# Power_Main_Regulators.net
KiCad netlist of a schematic drawn in Altium Designer
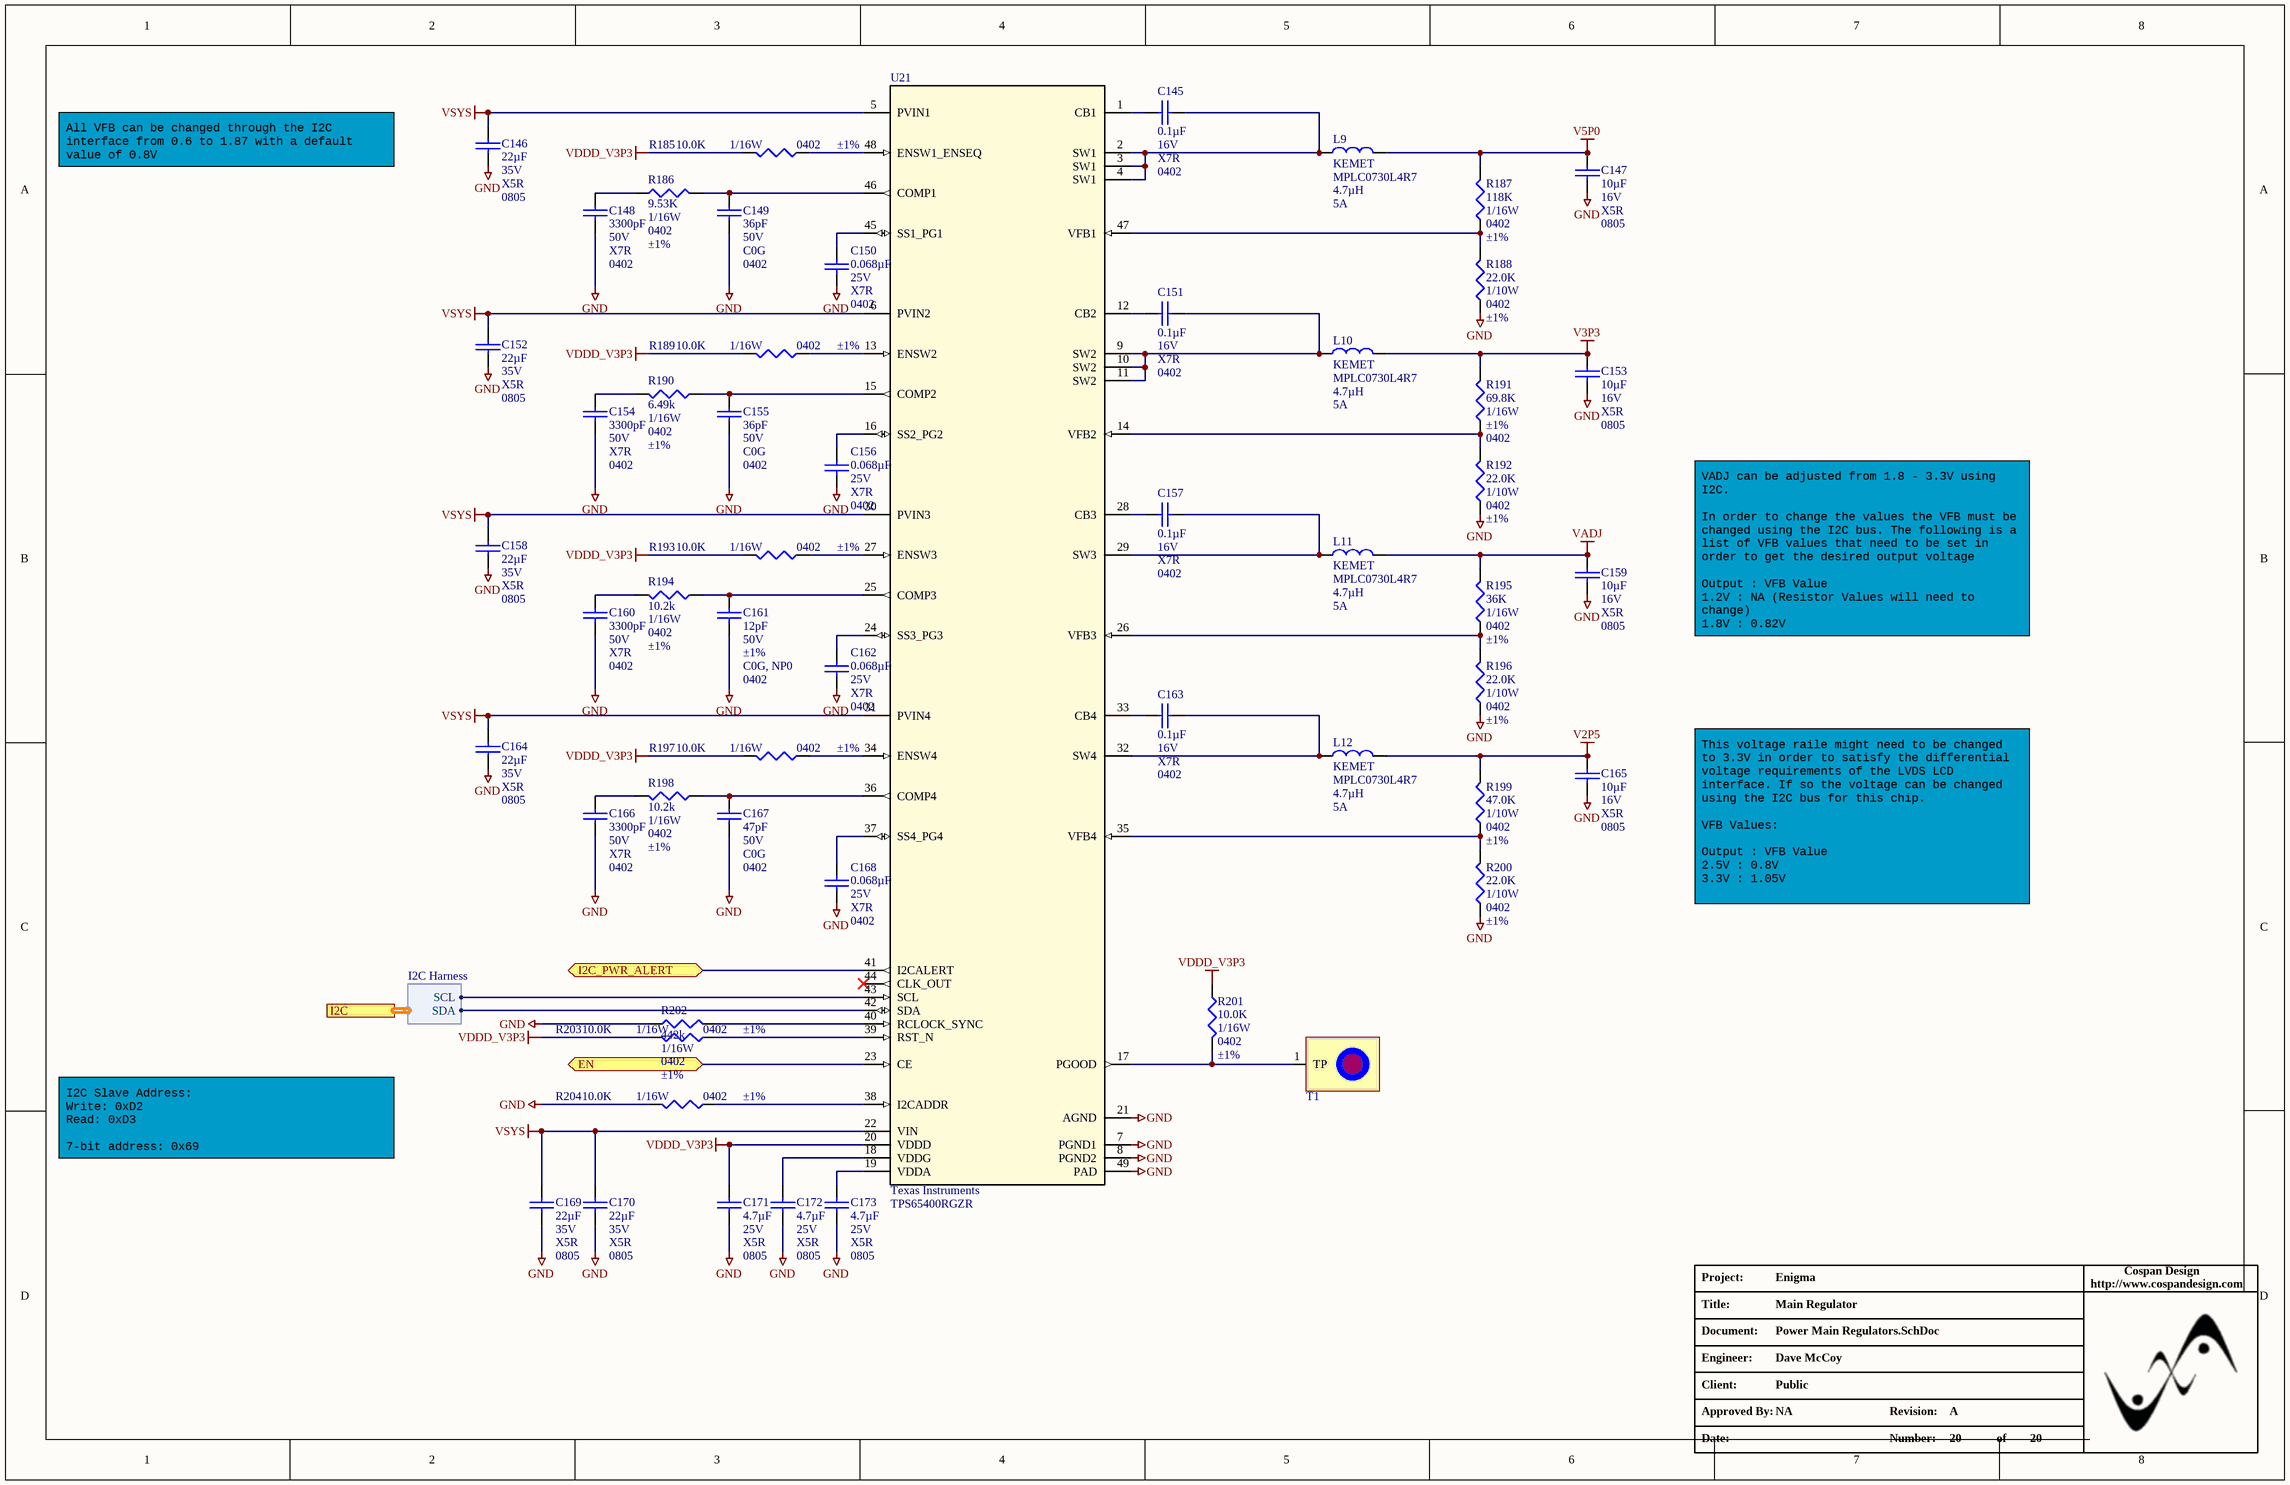
[diagram p0: Power Main Regulators.SchDoc]

(export (version "E")
  (design (tool "Eeschema 10.0.6"))
  (components
    (comp (ref "C145")
      (value "0.1uF")
      (footprint "C_0402")
      (description "CAP CER .10UF 16V X7R 0402")
      (fields
        (field (name "MANUFACTURER") "Murata Electronics North America")
        (field (name "MANUFACTURER PART NUMBER") "GRM155R71C104KA88J")
        (field (name "CAPACITANCE") "0.1µF")
        (field (name "VOLTAGE - RATED") "16V")
        (field (name "TEMPERATURE COEFFICIENT") "X7R")
        (field (name "PACKAGE / CASE") "0402")
      )
      (libsource (lib "Main LibraryX") (part "C_0402_0.1UF_16V"))
    )
    (comp (ref "C146")
      (value "C_0805_22µF_35V")
      (footprint "C_ERA-0805")
      (description "CAP CER 22UF 35V X5R 0805")
      (fields
        (field (name "MANUFACTURER") "TDK Corporation")
        (field (name "MANUFACTURER PART NUMBER") "C2012X5R1V226M125AC")
        (field (name "CAPACITANCE") "22µF")
        (field (name "VOLTAGE - RATED") "35V")
        (field (name "TEMPERATURE COEFFICIENT") "X5R")
        (field (name "PACKAGE / CASE") "0805")
      )
      (libsource (lib "Cospan Design") (part "C_0805_22µF_35V"))
    )
    (comp (ref "C147")
      (value "10µF")
      (footprint "C_ERA-0805")
      (description "CAP CER 10uF 16V X5R 20% 0805")
      (fields
        (field (name "MANUFACTURER") "Taiyo Yuden")
        (field (name "MANUFACTURER PART NUMBER") "EMK212BJ106KG-T")
        (field (name "CAPACITANCE") "10µF")
        (field (name "VOLTAGE - RATED") "16V")
        (field (name "TEMPERATURE COEFFICIENT") "X5R")
        (field (name "PACKAGE / CASE") "0805")
      )
      (libsource (lib "Main LibraryX") (part "C_0805_10UF_16V"))
    )
    (comp (ref "C148")
      (value "C_0402_3.3nF_50V")
      (footprint "C_ERA-0402")
      (fields
        (field (name "MANUFACTURER") "Murata Electronics North America")
        (field (name "MANUFACTURER PART NUMBER") "GRM155R71H332KA01D")
        (field (name "TOLERANCE") "±10%")
        (field (name "CAPACITANCE") "3300pF")
        (field (name "VOLTAGE - RATED") "50V")
        (field (name "TEMPERATURE COEFFICIENT") "X7R")
        (field (name "PACKAGE / CASE") "0402")
      )
      (libsource (lib "Main LibraryX") (part "C_0402_3.3nF_50V"))
    )
    (comp (ref "C149")
      (value "C_0402_36pF")
      (footprint "C_0402")
      (description "CAP CER 36PF 50V NP0 0402")
      (fields
        (field (name "MANUFACTURER") "Samsung Electro-Mechanics America, Inc.")
        (field (name "MANUFACTURER PART NUMBER") "CL05C360JB5NNNC")
        (field (name "CAPACITANCE") "36pF")
        (field (name "VOLTAGE - RATED") "50V")
        (field (name "TEMPERATURE COEFFICIENT") "C0G")
        (field (name "PACKAGE / CASE") "0402")
      )
      (libsource (lib "Cospan Design") (part "C_0402_36pF"))
    )
    (comp (ref "C150")
      (value "C_0402_68nF")
      (footprint "C_0402")
      (description "CAP CER 0.068UF 25V X7R 0402")
      (fields
        (field (name "MANUFACTURER") "Murata Electronics North America")
        (field (name "MANUFACTURER PART NUMBER") "GRM155R71E683KE14D")
        (field (name "CAPACITANCE") "0.068µF")
        (field (name "VOLTAGE - RATED") "25V")
        (field (name "TEMPERATURE COEFFICIENT") "X7R")
        (field (name "PACKAGE / CASE") "0402")
      )
      (libsource (lib "Cospan Design") (part "C_0402_68nF"))
    )
    (comp (ref "C151")
      (value "0.1uF")
      (footprint "C_0402")
      (description "CAP CER .10UF 16V X7R 0402")
      (fields
        (field (name "MANUFACTURER") "Murata Electronics North America")
        (field (name "MANUFACTURER PART NUMBER") "GRM155R71C104KA88J")
        (field (name "CAPACITANCE") "0.1µF")
        (field (name "VOLTAGE - RATED") "16V")
        (field (name "TEMPERATURE COEFFICIENT") "X7R")
        (field (name "PACKAGE / CASE") "0402")
      )
      (libsource (lib "Main LibraryX") (part "C_0402_0.1UF_16V"))
    )
    (comp (ref "C152")
      (value "C_0805_22µF_35V")
      (footprint "C_ERA-0805")
      (description "CAP CER 22UF 35V X5R 0805")
      (fields
        (field (name "MANUFACTURER") "TDK Corporation")
        (field (name "MANUFACTURER PART NUMBER") "C2012X5R1V226M125AC")
        (field (name "CAPACITANCE") "22µF")
        (field (name "VOLTAGE - RATED") "35V")
        (field (name "TEMPERATURE COEFFICIENT") "X5R")
        (field (name "PACKAGE / CASE") "0805")
      )
      (libsource (lib "Cospan Design") (part "C_0805_22µF_35V"))
    )
    (comp (ref "C153")
      (value "10µF")
      (footprint "C_ERA-0805")
      (description "CAP CER 10uF 16V X5R 20% 0805")
      (fields
        (field (name "MANUFACTURER") "Taiyo Yuden")
        (field (name "MANUFACTURER PART NUMBER") "EMK212BJ106KG-T")
        (field (name "CAPACITANCE") "10µF")
        (field (name "VOLTAGE - RATED") "16V")
        (field (name "TEMPERATURE COEFFICIENT") "X5R")
        (field (name "PACKAGE / CASE") "0805")
      )
      (libsource (lib "Main LibraryX") (part "C_0805_10UF_16V"))
    )
    (comp (ref "C154")
      (value "C_0402_3.3nF_50V")
      (footprint "C_ERA-0402")
      (fields
        (field (name "MANUFACTURER") "Murata Electronics North America")
        (field (name "MANUFACTURER PART NUMBER") "GRM155R71H332KA01D")
        (field (name "TOLERANCE") "±10%")
        (field (name "CAPACITANCE") "3300pF")
        (field (name "VOLTAGE - RATED") "50V")
        (field (name "TEMPERATURE COEFFICIENT") "X7R")
        (field (name "PACKAGE / CASE") "0402")
      )
      (libsource (lib "Main LibraryX") (part "C_0402_3.3nF_50V"))
    )
    (comp (ref "C155")
      (value "C_0402_36pF")
      (footprint "C_0402")
      (description "CAP CER 36PF 50V NP0 0402")
      (fields
        (field (name "MANUFACTURER") "Samsung Electro-Mechanics America, Inc.")
        (field (name "MANUFACTURER PART NUMBER") "CL05C360JB5NNNC")
        (field (name "CAPACITANCE") "36pF")
        (field (name "VOLTAGE - RATED") "50V")
        (field (name "TEMPERATURE COEFFICIENT") "C0G")
        (field (name "PACKAGE / CASE") "0402")
      )
      (libsource (lib "Cospan Design") (part "C_0402_36pF"))
    )
    (comp (ref "C156")
      (value "C_0402_68nF")
      (footprint "C_0402")
      (description "CAP CER 0.068UF 25V X7R 0402")
      (fields
        (field (name "MANUFACTURER") "Murata Electronics North America")
        (field (name "MANUFACTURER PART NUMBER") "GRM155R71E683KE14D")
        (field (name "CAPACITANCE") "0.068µF")
        (field (name "VOLTAGE - RATED") "25V")
        (field (name "TEMPERATURE COEFFICIENT") "X7R")
        (field (name "PACKAGE / CASE") "0402")
      )
      (libsource (lib "Cospan Design") (part "C_0402_68nF"))
    )
    (comp (ref "C157")
      (value "0.1uF")
      (footprint "C_0402")
      (description "CAP CER .10UF 16V X7R 0402")
      (fields
        (field (name "MANUFACTURER") "Murata Electronics North America")
        (field (name "MANUFACTURER PART NUMBER") "GRM155R71C104KA88J")
        (field (name "CAPACITANCE") "0.1µF")
        (field (name "VOLTAGE - RATED") "16V")
        (field (name "TEMPERATURE COEFFICIENT") "X7R")
        (field (name "PACKAGE / CASE") "0402")
      )
      (libsource (lib "Main LibraryX") (part "C_0402_0.1UF_16V"))
    )
    (comp (ref "C158")
      (value "C_0805_22µF_35V")
      (footprint "C_ERA-0805")
      (description "CAP CER 22UF 35V X5R 0805")
      (fields
        (field (name "MANUFACTURER") "TDK Corporation")
        (field (name "MANUFACTURER PART NUMBER") "C2012X5R1V226M125AC")
        (field (name "CAPACITANCE") "22µF")
        (field (name "VOLTAGE - RATED") "35V")
        (field (name "TEMPERATURE COEFFICIENT") "X5R")
        (field (name "PACKAGE / CASE") "0805")
      )
      (libsource (lib "Cospan Design") (part "C_0805_22µF_35V"))
    )
    (comp (ref "C159")
      (value "10µF")
      (footprint "C_ERA-0805")
      (description "CAP CER 10uF 16V X5R 20% 0805")
      (fields
        (field (name "MANUFACTURER") "Taiyo Yuden")
        (field (name "MANUFACTURER PART NUMBER") "EMK212BJ106KG-T")
        (field (name "CAPACITANCE") "10µF")
        (field (name "VOLTAGE - RATED") "16V")
        (field (name "TEMPERATURE COEFFICIENT") "X5R")
        (field (name "PACKAGE / CASE") "0805")
      )
      (libsource (lib "Main LibraryX") (part "C_0805_10UF_16V"))
    )
    (comp (ref "C160")
      (value "C_0402_3.3nF_50V")
      (footprint "C_ERA-0402")
      (fields
        (field (name "MANUFACTURER") "Murata Electronics North America")
        (field (name "MANUFACTURER PART NUMBER") "GRM155R71H332KA01D")
        (field (name "TOLERANCE") "±10%")
        (field (name "CAPACITANCE") "3300pF")
        (field (name "VOLTAGE - RATED") "50V")
        (field (name "TEMPERATURE COEFFICIENT") "X7R")
        (field (name "PACKAGE / CASE") "0402")
      )
      (libsource (lib "Main LibraryX") (part "C_0402_3.3nF_50V"))
    )
    (comp (ref "C161")
      (value "12pF")
      (footprint "C_ERA-0402")
      (description "CAP CER 12PF 50V 5% C0G 0402")
      (fields
        (field (name "MANUFACTURER") "Murata Electronics North America")
        (field (name "MANUFACTURER PART NUMBER") "GRM1555C1H120FA01D")
        (field (name "CAPACITANCE") "12pF")
        (field (name "VOLTAGE - RATED") "50V")
        (field (name "TOLERANCE") "±1%")
        (field (name "TEMPERATURE COEFFICIENT") "C0G, NP0")
        (field (name "PACKAGE / CASE") "0402")
      )
      (libsource (lib "Main LibraryX") (part "C_0402_12PF_50V"))
    )
    (comp (ref "C162")
      (value "C_0402_68nF")
      (footprint "C_0402")
      (description "CAP CER 0.068UF 25V X7R 0402")
      (fields
        (field (name "MANUFACTURER") "Murata Electronics North America")
        (field (name "MANUFACTURER PART NUMBER") "GRM155R71E683KE14D")
        (field (name "CAPACITANCE") "0.068µF")
        (field (name "VOLTAGE - RATED") "25V")
        (field (name "TEMPERATURE COEFFICIENT") "X7R")
        (field (name "PACKAGE / CASE") "0402")
      )
      (libsource (lib "Cospan Design") (part "C_0402_68nF"))
    )
    (comp (ref "C163")
      (value "0.1uF")
      (footprint "C_0402")
      (description "CAP CER .10UF 16V X7R 0402")
      (fields
        (field (name "MANUFACTURER") "Murata Electronics North America")
        (field (name "MANUFACTURER PART NUMBER") "GRM155R71C104KA88J")
        (field (name "CAPACITANCE") "0.1µF")
        (field (name "VOLTAGE - RATED") "16V")
        (field (name "TEMPERATURE COEFFICIENT") "X7R")
        (field (name "PACKAGE / CASE") "0402")
      )
      (libsource (lib "Main LibraryX") (part "C_0402_0.1UF_16V"))
    )
    (comp (ref "C164")
      (value "C_0805_22µF_35V")
      (footprint "C_ERA-0805")
      (description "CAP CER 22UF 35V X5R 0805")
      (fields
        (field (name "MANUFACTURER") "TDK Corporation")
        (field (name "MANUFACTURER PART NUMBER") "C2012X5R1V226M125AC")
        (field (name "CAPACITANCE") "22µF")
        (field (name "VOLTAGE - RATED") "35V")
        (field (name "TEMPERATURE COEFFICIENT") "X5R")
        (field (name "PACKAGE / CASE") "0805")
      )
      (libsource (lib "Cospan Design") (part "C_0805_22µF_35V"))
    )
    (comp (ref "C165")
      (value "10µF")
      (footprint "C_ERA-0805")
      (description "CAP CER 10uF 16V X5R 20% 0805")
      (fields
        (field (name "MANUFACTURER") "Taiyo Yuden")
        (field (name "MANUFACTURER PART NUMBER") "EMK212BJ106KG-T")
        (field (name "CAPACITANCE") "10µF")
        (field (name "VOLTAGE - RATED") "16V")
        (field (name "TEMPERATURE COEFFICIENT") "X5R")
        (field (name "PACKAGE / CASE") "0805")
      )
      (libsource (lib "Main LibraryX") (part "C_0805_10UF_16V"))
    )
    (comp (ref "C166")
      (value "C_0402_3.3nF_50V")
      (footprint "C_ERA-0402")
      (fields
        (field (name "MANUFACTURER") "Murata Electronics North America")
        (field (name "MANUFACTURER PART NUMBER") "GRM155R71H332KA01D")
        (field (name "TOLERANCE") "±10%")
        (field (name "CAPACITANCE") "3300pF")
        (field (name "VOLTAGE - RATED") "50V")
        (field (name "TEMPERATURE COEFFICIENT") "X7R")
        (field (name "PACKAGE / CASE") "0402")
      )
      (libsource (lib "Main LibraryX") (part "C_0402_3.3nF_50V"))
    )
    (comp (ref "C167")
      (value "47pF")
      (footprint "C_0402")
      (description "CAP CER 47PF 50V 5% C0G 0402")
      (fields
        (field (name "MANUFACTURER") "Murata Electronics North America")
        (field (name "MANUFACTURER PART NUMBER") "GRM1555C1H470JA01D")
        (field (name "CAPACITANCE") "47pF")
        (field (name "VOLTAGE - RATED") "50V")
        (field (name "TEMPERATURE COEFFICIENT") "C0G")
        (field (name "PACKAGE / CASE") "0402")
      )
      (libsource (lib "Main Library") (part "C_0402_47p_50V"))
    )
    (comp (ref "C168")
      (value "C_0402_68nF")
      (footprint "C_0402")
      (description "CAP CER 0.068UF 25V X7R 0402")
      (fields
        (field (name "MANUFACTURER") "Murata Electronics North America")
        (field (name "MANUFACTURER PART NUMBER") "GRM155R71E683KE14D")
        (field (name "CAPACITANCE") "0.068µF")
        (field (name "VOLTAGE - RATED") "25V")
        (field (name "TEMPERATURE COEFFICIENT") "X7R")
        (field (name "PACKAGE / CASE") "0402")
      )
      (libsource (lib "Cospan Design") (part "C_0402_68nF"))
    )
    (comp (ref "C169")
      (value "C_0805_22µF_35V")
      (footprint "C_ERA-0805")
      (description "CAP CER 22UF 35V X5R 0805")
      (fields
        (field (name "MANUFACTURER") "TDK Corporation")
        (field (name "MANUFACTURER PART NUMBER") "C2012X5R1V226M125AC")
        (field (name "CAPACITANCE") "22µF")
        (field (name "VOLTAGE - RATED") "35V")
        (field (name "TEMPERATURE COEFFICIENT") "X5R")
        (field (name "PACKAGE / CASE") "0805")
      )
      (libsource (lib "Cospan Design") (part "C_0805_22µF_35V"))
    )
    (comp (ref "C170")
      (value "C_0805_22µF_35V")
      (footprint "C_ERA-0805")
      (description "CAP CER 22UF 35V X5R 0805")
      (fields
        (field (name "MANUFACTURER") "TDK Corporation")
        (field (name "MANUFACTURER PART NUMBER") "C2012X5R1V226M125AC")
        (field (name "CAPACITANCE") "22µF")
        (field (name "VOLTAGE - RATED") "35V")
        (field (name "TEMPERATURE COEFFICIENT") "X5R")
        (field (name "PACKAGE / CASE") "0805")
      )
      (libsource (lib "Cospan Design") (part "C_0805_22µF_35V"))
    )
    (comp (ref "C171")
      (value "4.7µF")
      (footprint "C_ERA-0805")
      (description "CAP CER 4.7UF 25V 10% X5R 0805")
      (fields
        (field (name "MANUFACTURER") "Taiyo Yuden")
        (field (name "MANUFACTURER PART NUMBER") "TMK212BJ475KG-T")
        (field (name "CAPACITANCE") "4.7µF")
        (field (name "VOLTAGE - RATED") "25V")
        (field (name "TEMPERATURE COEFFICIENT") "X5R")
        (field (name "PACKAGE / CASE") "0805")
      )
      (libsource (lib "Main Library") (part "C_0805_4.7µF_25V"))
    )
    (comp (ref "C172")
      (value "4.7µF")
      (footprint "C_ERA-0805")
      (description "CAP CER 4.7UF 25V 10% X5R 0805")
      (fields
        (field (name "MANUFACTURER") "Taiyo Yuden")
        (field (name "MANUFACTURER PART NUMBER") "TMK212BJ475KG-T")
        (field (name "CAPACITANCE") "4.7µF")
        (field (name "VOLTAGE - RATED") "25V")
        (field (name "TEMPERATURE COEFFICIENT") "X5R")
        (field (name "PACKAGE / CASE") "0805")
      )
      (libsource (lib "Main Library") (part "C_0805_4.7µF_25V"))
    )
    (comp (ref "C173")
      (value "4.7µF")
      (footprint "C_ERA-0805")
      (description "CAP CER 4.7UF 25V 10% X5R 0805")
      (fields
        (field (name "MANUFACTURER") "Taiyo Yuden")
        (field (name "MANUFACTURER PART NUMBER") "TMK212BJ475KG-T")
        (field (name "CAPACITANCE") "4.7µF")
        (field (name "VOLTAGE - RATED") "25V")
        (field (name "TEMPERATURE COEFFICIENT") "X5R")
        (field (name "PACKAGE / CASE") "0805")
      )
      (libsource (lib "Main Library") (part "C_0805_4.7µF_25V"))
    )
    (comp (ref "L9")
      (value "L_MPLC0730L4R7")
      (footprint "KEM_L9004_MPLC")
      (description "FIXED IND 4.7UH 5A 41 MOHM SMD")
      (fields
        (field (name "TOLERANCE") "±20%")
        (field (name "MANUFACTURER") "KEMET")
        (field (name "MANUFACTURER PART NUMBER") "MPLC0730L4R7")
        (field (name "INDUCTANCE") "4.7µH")
        (field (name "MAX DC CURRENT") "5A")
      )
      (libsource (lib "Cospan Design") (part "L_MPLC0730L4R7"))
    )
    (comp (ref "L10")
      (value "L_MPLC0730L4R7")
      (footprint "KEM_L9004_MPLC")
      (description "FIXED IND 4.7UH 5A 41 MOHM SMD")
      (fields
        (field (name "TOLERANCE") "±20%")
        (field (name "MANUFACTURER") "KEMET")
        (field (name "MANUFACTURER PART NUMBER") "MPLC0730L4R7")
        (field (name "INDUCTANCE") "4.7µH")
        (field (name "MAX DC CURRENT") "5A")
      )
      (libsource (lib "Cospan Design") (part "L_MPLC0730L4R7"))
    )
    (comp (ref "L11")
      (value "L_MPLC0730L4R7")
      (footprint "KEM_L9004_MPLC")
      (description "FIXED IND 4.7UH 5A 41 MOHM SMD")
      (fields
        (field (name "TOLERANCE") "±20%")
        (field (name "MANUFACTURER") "KEMET")
        (field (name "MANUFACTURER PART NUMBER") "MPLC0730L4R7")
        (field (name "INDUCTANCE") "4.7µH")
        (field (name "MAX DC CURRENT") "5A")
      )
      (libsource (lib "Cospan Design") (part "L_MPLC0730L4R7"))
    )
    (comp (ref "L12")
      (value "L_MPLC0730L4R7")
      (footprint "KEM_L9004_MPLC")
      (description "FIXED IND 4.7UH 5A 41 MOHM SMD")
      (fields
        (field (name "TOLERANCE") "±20%")
        (field (name "MANUFACTURER") "KEMET")
        (field (name "MANUFACTURER PART NUMBER") "MPLC0730L4R7")
        (field (name "INDUCTANCE") "4.7µH")
        (field (name "MAX DC CURRENT") "5A")
      )
      (libsource (lib "Cospan Design") (part "L_MPLC0730L4R7"))
    )
    (comp (ref "R185")
      (value "R_0402_10.0K")
      (footprint "R_0402")
      (description "RES 10.0K OHM 1/16W 1% 0402 SMD")
      (fields
        (field (name "MANUFACTURER") "Stackpole Electronics Inc")
        (field (name "MANUFACTURER PART NUMBER") "RMCF0402FT10K0")
        (field (name "RESISTANCE IN OHMS") "10.0K")
        (field (name "POWER (WATTS)") "1/16W")
        (field (name "CASE") "0402")
        (field (name "TOLERANCE") "±1%")
      )
      (libsource (lib "Cospan Design") (part "R_0402_10.0K"))
    )
    (comp (ref "R186")
      (value "R_0402_9.53K")
      (footprint "R_0402")
      (description "RES SMD 9.53K OHM 1% 1/16W 0402")
      (fields
        (field (name "MANUFACTURER") "Yageo")
        (field (name "MANUFACTURER PART NUMBER") "RC0402FR-079K53L")
        (field (name "RESISTANCE IN OHMS") "9.53K")
        (field (name "POWER (WATTS)") "1/16W")
        (field (name "CASE") "0402")
        (field (name "TOLERANCE") "±1%")
      )
      (libsource (lib "Cospan Design") (part "R_0402_9.53K"))
    )
    (comp (ref "R187")
      (value "R_0402_118K")
      (footprint "R_0402")
      (description "RES SMD 118K OHM 1% 1/16W 0402")
      (fields
        (field (name "MANUFACTURER") "Stackpole Electronics Inc")
        (field (name "MANUFACTURER PART NUMBER") "RMCF0402FT118K")
        (field (name "RESISTANCE IN OHMS") "118K")
        (field (name "POWER (WATTS)") "1/16W")
        (field (name "CASE") "0402")
        (field (name "TOLERANCE") "±1%")
      )
      (libsource (lib "Cospan Design") (part "R_0402_118K"))
    )
    (comp (ref "R188")
      (value "R_0402_22.0K")
      (footprint "R_0402")
      (description "RES 22.0K OHM 1/10W 1% 0402 SMD")
      (fields
        (field (name "MANUFACTURER") "Vishay Dale")
        (field (name "MANUFACTURER PART NUMBER") "CRCW040222K0FKED")
        (field (name "RESISTANCE IN OHMS") "22.0K")
        (field (name "POWER (WATTS)") "1/10W")
        (field (name "CASE") "0402")
        (field (name "TOLERANCE") "±1%")
      )
      (libsource (lib "Main Library") (part "R_0402_22.0K"))
    )
    (comp (ref "R189")
      (value "R_0402_10.0K")
      (footprint "R_0402")
      (description "RES 10.0K OHM 1/16W 1% 0402 SMD")
      (fields
        (field (name "MANUFACTURER") "Stackpole Electronics Inc")
        (field (name "MANUFACTURER PART NUMBER") "RMCF0402FT10K0")
        (field (name "RESISTANCE IN OHMS") "10.0K")
        (field (name "POWER (WATTS)") "1/16W")
        (field (name "CASE") "0402")
        (field (name "TOLERANCE") "±1%")
      )
      (libsource (lib "Cospan Design") (part "R_0402_10.0K"))
    )
    (comp (ref "R190")
      (value "R_0402_6.49k")
      (footprint "R_0402")
      (description "RES SMD 6.49K OHM 1% 1/16W 0402")
      (fields
        (field (name "MANUFACTURER") "Samsung Electro-Mechanics America, Inc.")
        (field (name "MANUFACTURER PART NUMBER") "RC1005F6491CS")
        (field (name "RESISTANCE IN OHMS") "6.49k")
        (field (name "POWER (WATTS)") "1/16W")
        (field (name "CASE") "0402")
        (field (name "TOLERANCE") "±1%")
      )
      (libsource (lib "Cospan Design") (part "R_0402_6.49k"))
    )
    (comp (ref "R191")
      (value "R_0402_69.8K")
      (footprint "R_0402")
      (description "RES 69.8K OHM 1/16W 1% 0402 SMD")
      (fields
        (field (name "MANUFACTURER") "Yageo")
        (field (name "MANUFACTURER PART NUMBER") "RC0402FR-0769K8L")
        (field (name "RESISTANCE IN OHMS") "69.8K")
        (field (name "POWER (WATTS)") "1/16W")
        (field (name "TOLERANCE") "±1%")
        (field (name "CASE") "0402")
      )
      (libsource (lib "Main LibraryX") (part "R_0402_69.8K"))
    )
    (comp (ref "R192")
      (value "R_0402_22.0K")
      (footprint "R_0402")
      (description "RES 22.0K OHM 1/10W 1% 0402 SMD")
      (fields
        (field (name "MANUFACTURER") "Vishay Dale")
        (field (name "MANUFACTURER PART NUMBER") "CRCW040222K0FKED")
        (field (name "RESISTANCE IN OHMS") "22.0K")
        (field (name "POWER (WATTS)") "1/10W")
        (field (name "CASE") "0402")
        (field (name "TOLERANCE") "±1%")
      )
      (libsource (lib "Main Library") (part "R_0402_22.0K"))
    )
    (comp (ref "R193")
      (value "R_0402_10.0K")
      (footprint "R_0402")
      (description "RES 10.0K OHM 1/16W 1% 0402 SMD")
      (fields
        (field (name "MANUFACTURER") "Stackpole Electronics Inc")
        (field (name "MANUFACTURER PART NUMBER") "RMCF0402FT10K0")
        (field (name "RESISTANCE IN OHMS") "10.0K")
        (field (name "POWER (WATTS)") "1/16W")
        (field (name "CASE") "0402")
        (field (name "TOLERANCE") "±1%")
      )
      (libsource (lib "Cospan Design") (part "R_0402_10.0K"))
    )
    (comp (ref "R194")
      (value "R_0402_10.2k")
      (footprint "R_0402")
      (description "RES SMD 10.2K OHM 1% 1/16W 0402")
      (fields
        (field (name "MANUFACTURER") "Stackpole Electronics Inc.")
        (field (name "MANUFACTURER PART NUMBER") "RMCF0402FT10K2")
        (field (name "RESISTANCE IN OHMS") "10.2k")
        (field (name "POWER (WATTS)") "1/16W")
        (field (name "CASE") "0402")
        (field (name "TOLERANCE") "±1%")
      )
      (libsource (lib "Cospan Design") (part "R_0402_10.2k"))
    )
    (comp (ref "R195")
      (value "R_0402_36.0K")
      (footprint "R_0402")
      (description "RES 36.0K OHM 1/10W 1% 0402 SMD")
      (fields
        (field (name "MANUFACTURER") "Panasonic - ECG")
        (field (name "MANUFACTURER PART NUMBER") "ERJ-2RKF3602X")
        (field (name "RESISTANCE IN OHMS") "36K")
        (field (name "POWER (WATTS)") "1/16W")
        (field (name "CASE") "0402")
        (field (name "TOLERANCE") "±1%")
      )
      (libsource (lib "Main Library") (part "R_0402_36.0K"))
    )
    (comp (ref "R196")
      (value "R_0402_22.0K")
      (footprint "R_0402")
      (description "RES 22.0K OHM 1/10W 1% 0402 SMD")
      (fields
        (field (name "MANUFACTURER") "Vishay Dale")
        (field (name "MANUFACTURER PART NUMBER") "CRCW040222K0FKED")
        (field (name "RESISTANCE IN OHMS") "22.0K")
        (field (name "POWER (WATTS)") "1/10W")
        (field (name "CASE") "0402")
        (field (name "TOLERANCE") "±1%")
      )
      (libsource (lib "Main Library") (part "R_0402_22.0K"))
    )
    (comp (ref "R197")
      (value "R_0402_10.0K")
      (footprint "R_0402")
      (description "RES 10.0K OHM 1/16W 1% 0402 SMD")
      (fields
        (field (name "MANUFACTURER") "Stackpole Electronics Inc")
        (field (name "MANUFACTURER PART NUMBER") "RMCF0402FT10K0")
        (field (name "RESISTANCE IN OHMS") "10.0K")
        (field (name "POWER (WATTS)") "1/16W")
        (field (name "CASE") "0402")
        (field (name "TOLERANCE") "±1%")
      )
      (libsource (lib "Cospan Design") (part "R_0402_10.0K"))
    )
    (comp (ref "R198")
      (value "R_0402_10.2k")
      (footprint "R_0402")
      (description "RES SMD 10.2K OHM 1% 1/16W 0402")
      (fields
        (field (name "MANUFACTURER") "Stackpole Electronics Inc.")
        (field (name "MANUFACTURER PART NUMBER") "RMCF0402FT10K2")
        (field (name "RESISTANCE IN OHMS") "10.2k")
        (field (name "POWER (WATTS)") "1/16W")
        (field (name "CASE") "0402")
        (field (name "TOLERANCE") "±1%")
      )
      (libsource (lib "Cospan Design") (part "R_0402_10.2k"))
    )
    (comp (ref "R199")
      (value "R_0402_47.0K")
      (footprint "R_0402")
      (description "RES 47.0K OHM 1/10W 1% 0402 SMD")
      (fields
        (field (name "MANUFACTURER") "Panasonic - ECG")
        (field (name "MANUFACTURER PART NUMBER") "ERJ-2RKF4702X")
        (field (name "RESISTANCE IN OHMS") "47.0K")
        (field (name "POWER (WATTS)") "1/10W")
        (field (name "CASE") "0402")
        (field (name "TOLERANCE") "±1%")
      )
      (libsource (lib "Main Library") (part "R_0402_47.0K"))
    )
    (comp (ref "R200")
      (value "R_0402_22.0K")
      (footprint "R_0402")
      (description "RES 22.0K OHM 1/10W 1% 0402 SMD")
      (fields
        (field (name "MANUFACTURER") "Vishay Dale")
        (field (name "MANUFACTURER PART NUMBER") "CRCW040222K0FKED")
        (field (name "RESISTANCE IN OHMS") "22.0K")
        (field (name "POWER (WATTS)") "1/10W")
        (field (name "CASE") "0402")
        (field (name "TOLERANCE") "±1%")
      )
      (libsource (lib "Main Library") (part "R_0402_22.0K"))
    )
    (comp (ref "R201")
      (value "R_0402_10.0K")
      (footprint "R_0402")
      (description "RES 10.0K OHM 1/16W 1% 0402 SMD")
      (fields
        (field (name "MANUFACTURER") "Stackpole Electronics Inc")
        (field (name "MANUFACTURER PART NUMBER") "RMCF0402FT10K0")
        (field (name "RESISTANCE IN OHMS") "10.0K")
        (field (name "POWER (WATTS)") "1/16W")
        (field (name "CASE") "0402")
        (field (name "TOLERANCE") "±1%")
      )
      (libsource (lib "Cospan Design") (part "R_0402_10.0K"))
    )
    (comp (ref "R202")
      (value "R_0402_442k")
      (footprint "R_0402")
      (description "RES SMD 442K OHM 1% 1/16W 0402")
      (fields
        (field (name "MANUFACTURER") "Yageo")
        (field (name "MANUFACTURER PART NUMBER") "RC0402FR-07442KL")
        (field (name "RESISTANCE IN OHMS") "442k")
        (field (name "POWER (WATTS)") "1/16W")
        (field (name "CASE") "0402")
        (field (name "TOLERANCE") "±1%")
      )
      (libsource (lib "Cospan Design") (part "R_0402_442k"))
    )
    (comp (ref "R203")
      (value "R_0402_10.0K")
      (footprint "R_0402")
      (description "RES 10.0K OHM 1/16W 1% 0402 SMD")
      (fields
        (field (name "MANUFACTURER") "Stackpole Electronics Inc")
        (field (name "MANUFACTURER PART NUMBER") "RMCF0402FT10K0")
        (field (name "RESISTANCE IN OHMS") "10.0K")
        (field (name "POWER (WATTS)") "1/16W")
        (field (name "CASE") "0402")
        (field (name "TOLERANCE") "±1%")
      )
      (libsource (lib "Cospan Design") (part "R_0402_10.0K"))
    )
    (comp (ref "R204")
      (value "R_0402_10.0K")
      (footprint "R_0402")
      (description "RES 10.0K OHM 1/16W 1% 0402 SMD")
      (fields
        (field (name "MANUFACTURER") "Stackpole Electronics Inc")
        (field (name "MANUFACTURER PART NUMBER") "RMCF0402FT10K0")
        (field (name "RESISTANCE IN OHMS") "10.0K")
        (field (name "POWER (WATTS)") "1/16W")
        (field (name "CASE") "0402")
        (field (name "TOLERANCE") "±1%")
      )
      (libsource (lib "Cospan Design") (part "R_0402_10.0K"))
    )
    (comp (ref "T1")
      (value "TEST_POINT_SMALL")
      (footprint "TestPointSmall")
      (description "OSCILLOSCOPE TEST POINT")
      (libsource (lib "Main Library") (part "TEST_POINT_SMALL"))
    )
    (comp (ref "U21")
      (value "U_TPS65400RGZR")
      (footprint "RGZ0048B")
      (description "IC REG BUCK ADJ 4A/2A QD 48VQFN")
      (fields
        (field (name "MANUFACTURER") "Texas Instruments")
        (field (name "MANUFACTURER PART NUMBER") "TPS65400RGZR")
      )
      (libsource (lib "Cospan Design") (part "U_TPS65400RGZR"))
    )
  )
  (nets
    (net (code "3") (name "/EN") (class "Default")
      (node (ref "U21") (pin "23") (pinfunction "CE_23") (pintype "input"))
    )
    (net (code "4") (name "/I2C_PWR_ALERT") (class "Default")
      (node (ref "U21") (pin "41") (pinfunction "I2CALERT_41") (pintype "output"))
    )
    (net (code "5") (name "/SCL") (class "Default")
      (node (ref "U21") (pin "43") (pinfunction "SCL_43") (pintype "input"))
    )
    (net (code "6") (name "/SDA") (class "Default")
      (node (ref "U21") (pin "42") (pinfunction "SDA_42") (pintype "bidirectional"))
    )
    (net (code "8") (name "GND") (class "Default")
      (node (ref "C146") (pin "1") (pinfunction "1_1") (pintype "passive"))
      (node (ref "C147") (pin "1") (pinfunction "1_1") (pintype "passive"))
      (node (ref "C148") (pin "1") (pinfunction "1_1") (pintype "passive"))
      (node (ref "C149") (pin "1") (pinfunction "1_1") (pintype "passive"))
      (node (ref "C150") (pin "1") (pinfunction "1_1") (pintype "passive"))
      (node (ref "C152") (pin "1") (pinfunction "1_1") (pintype "passive"))
      (node (ref "C153") (pin "1") (pinfunction "1_1") (pintype "passive"))
      (node (ref "C154") (pin "1") (pinfunction "1_1") (pintype "passive"))
      (node (ref "C155") (pin "1") (pinfunction "1_1") (pintype "passive"))
      (node (ref "C156") (pin "1") (pinfunction "1_1") (pintype "passive"))
      (node (ref "C158") (pin "1") (pinfunction "1_1") (pintype "passive"))
      (node (ref "C159") (pin "1") (pinfunction "1_1") (pintype "passive"))
      (node (ref "C160") (pin "1") (pinfunction "1_1") (pintype "passive"))
      (node (ref "C161") (pin "1") (pinfunction "1_1") (pintype "passive"))
      (node (ref "C162") (pin "1") (pinfunction "1_1") (pintype "passive"))
      (node (ref "C164") (pin "1") (pinfunction "1_1") (pintype "passive"))
      (node (ref "C165") (pin "1") (pinfunction "1_1") (pintype "passive"))
      (node (ref "C166") (pin "1") (pinfunction "1_1") (pintype "passive"))
      (node (ref "C167") (pin "1") (pinfunction "1_1") (pintype "passive"))
      (node (ref "C168") (pin "1") (pinfunction "1_1") (pintype "passive"))
      (node (ref "C169") (pin "1") (pinfunction "1_1") (pintype "passive"))
      (node (ref "C170") (pin "1") (pinfunction "1_1") (pintype "passive"))
      (node (ref "C171") (pin "1") (pinfunction "1_1") (pintype "passive"))
      (node (ref "C172") (pin "1") (pinfunction "1_1") (pintype "passive"))
      (node (ref "C173") (pin "1") (pinfunction "1_1") (pintype "passive"))
      (node (ref "R188") (pin "2") (pinfunction "2_2") (pintype "passive"))
      (node (ref "R192") (pin "2") (pinfunction "2_2") (pintype "passive"))
      (node (ref "R196") (pin "2") (pinfunction "2_2") (pintype "passive"))
      (node (ref "R200") (pin "2") (pinfunction "2_2") (pintype "passive"))
      (node (ref "R202") (pin "2") (pinfunction "2_2") (pintype "passive"))
      (node (ref "R204") (pin "1") (pinfunction "1_1") (pintype "passive"))
      (node (ref "U21") (pin "21") (pinfunction "AGND_21") (pintype "power_in"))
      (node (ref "U21") (pin "49") (pinfunction "PAD_49") (pintype "passive"))
      (node (ref "U21") (pin "7") (pinfunction "PGND1_7") (pintype "power_in"))
      (node (ref "U21") (pin "8") (pinfunction "PGND2_8") (pintype "power_in"))
    )
    (net (code "9") (name "Net-(C145-Pad1)") (class "Default")
      (node (ref "C145") (pin "1") (pinfunction "1_1") (pintype "passive"))
      (node (ref "L9") (pin "2") (pintype "passive"))
      (node (ref "U21") (pin "2") (pinfunction "SW1_2") (pintype "power_in"))
      (node (ref "U21") (pin "3") (pinfunction "SW1_3") (pintype "power_in"))
      (node (ref "U21") (pin "4") (pinfunction "SW1_4") (pintype "power_in"))
    )
    (net (code "10") (name "Net-(C148-Pad2)") (class "Default")
      (node (ref "C148") (pin "2") (pinfunction "2_2") (pintype "passive"))
      (node (ref "R186") (pin "2") (pinfunction "2_2") (pintype "passive"))
    )
    (net (code "11") (name "Net-(C151-Pad1)") (class "Default")
      (node (ref "C151") (pin "1") (pinfunction "1_1") (pintype "passive"))
      (node (ref "L10") (pin "2") (pintype "passive"))
      (node (ref "U21") (pin "10") (pinfunction "SW2_10") (pintype "passive"))
      (node (ref "U21") (pin "11") (pinfunction "SW2_11") (pintype "power_in"))
      (node (ref "U21") (pin "9") (pinfunction "SW2_9") (pintype "power_in"))
    )
    (net (code "12") (name "Net-(C154-Pad2)") (class "Default")
      (node (ref "C154") (pin "2") (pinfunction "2_2") (pintype "passive"))
      (node (ref "R190") (pin "1") (pinfunction "1_1") (pintype "passive"))
    )
    (net (code "13") (name "Net-(C160-Pad2)") (class "Default")
      (node (ref "C160") (pin "2") (pinfunction "2_2") (pintype "passive"))
      (node (ref "R194") (pin "1") (pinfunction "1_1") (pintype "passive"))
    )
    (net (code "14") (name "Net-(C166-Pad2)") (class "Default")
      (node (ref "C166") (pin "2") (pinfunction "2_2") (pintype "passive"))
      (node (ref "R198") (pin "1") (pinfunction "1_1") (pintype "passive"))
    )
    (net (code "15") (name "Net-(T1-TP)") (class "Default")
      (node (ref "R201") (pin "1") (pinfunction "1_1") (pintype "passive"))
      (node (ref "T1") (pin "1") (pinfunction "TP_1") (pintype "passive"))
      (node (ref "U21") (pin "17") (pinfunction "PGOOD_17") (pintype "output"))
    )
    (net (code "16") (name "Net-(U21-CB1)") (class "Default")
      (node (ref "C145") (pin "2") (pinfunction "2_2") (pintype "passive"))
      (node (ref "U21") (pin "1") (pinfunction "CB1_1") (pintype "power_in"))
    )
    (net (code "17") (name "Net-(U21-CB2)") (class "Default")
      (node (ref "C151") (pin "2") (pinfunction "2_2") (pintype "passive"))
      (node (ref "U21") (pin "12") (pinfunction "CB2_12") (pintype "power_in"))
    )
    (net (code "18") (name "Net-(U21-CB3)") (class "Default")
      (node (ref "C157") (pin "2") (pinfunction "2_2") (pintype "passive"))
      (node (ref "U21") (pin "28") (pinfunction "CB3_28") (pintype "power_in"))
    )
    (net (code "19") (name "Net-(U21-CB4)") (class "Default")
      (node (ref "C163") (pin "2") (pinfunction "2_2") (pintype "passive"))
      (node (ref "U21") (pin "33") (pinfunction "CB4_33") (pintype "power_in"))
    )
    (net (code "20") (name "Net-(U21-COMP1)") (class "Default")
      (node (ref "C149") (pin "2") (pinfunction "2_2") (pintype "passive"))
      (node (ref "R186") (pin "1") (pinfunction "1_1") (pintype "passive"))
      (node (ref "U21") (pin "46") (pinfunction "COMP1_46") (pintype "output"))
    )
    (net (code "21") (name "Net-(U21-COMP2)") (class "Default")
      (node (ref "C155") (pin "2") (pinfunction "2_2") (pintype "passive"))
      (node (ref "R190") (pin "2") (pinfunction "2_2") (pintype "passive"))
      (node (ref "U21") (pin "15") (pinfunction "COMP2_15") (pintype "output"))
    )
    (net (code "22") (name "Net-(U21-COMP3)") (class "Default")
      (node (ref "C161") (pin "2") (pinfunction "2_2") (pintype "passive"))
      (node (ref "R194") (pin "2") (pinfunction "2_2") (pintype "passive"))
      (node (ref "U21") (pin "25") (pinfunction "COMP3_25") (pintype "output"))
    )
    (net (code "23") (name "Net-(U21-COMP4)") (class "Default")
      (node (ref "C167") (pin "2") (pinfunction "2_2") (pintype "passive"))
      (node (ref "R198") (pin "2") (pinfunction "2_2") (pintype "passive"))
      (node (ref "U21") (pin "36") (pinfunction "COMP4_36") (pintype "output"))
    )
    (net (code "24") (name "Net-(U21-ENSW1_ENSEQ)") (class "Default")
      (node (ref "R185") (pin "2") (pinfunction "2_2") (pintype "passive"))
      (node (ref "U21") (pin "48") (pinfunction "ENSW1_ENSEQ_48") (pintype "input"))
    )
    (net (code "25") (name "Net-(U21-ENSW2)") (class "Default")
      (node (ref "R189") (pin "2") (pinfunction "2_2") (pintype "passive"))
      (node (ref "U21") (pin "13") (pinfunction "ENSW2_13") (pintype "input"))
    )
    (net (code "26") (name "Net-(U21-ENSW3)") (class "Default")
      (node (ref "R193") (pin "2") (pinfunction "2_2") (pintype "passive"))
      (node (ref "U21") (pin "27") (pinfunction "ENSW3_27") (pintype "input"))
    )
    (net (code "27") (name "Net-(U21-ENSW4)") (class "Default")
      (node (ref "R197") (pin "2") (pinfunction "2_2") (pintype "passive"))
      (node (ref "U21") (pin "34") (pinfunction "ENSW4_34") (pintype "input"))
    )
    (net (code "28") (name "Net-(U21-I2CADDR)") (class "Default")
      (node (ref "R204") (pin "2") (pinfunction "2_2") (pintype "passive"))
      (node (ref "U21") (pin "38") (pinfunction "I2CADDR_38") (pintype "input"))
    )
    (net (code "29") (name "Net-(U21-RCLOCK_SYNC)") (class "Default")
      (node (ref "R202") (pin "1") (pinfunction "1_1") (pintype "passive"))
      (node (ref "U21") (pin "40") (pinfunction "RCLOCK_SYNC_40") (pintype "input"))
    )
    (net (code "30") (name "Net-(U21-RST_N)") (class "Default")
      (node (ref "R203") (pin "2") (pinfunction "2_2") (pintype "passive"))
      (node (ref "U21") (pin "39") (pinfunction "RST_N_39") (pintype "input"))
    )
    (net (code "31") (name "Net-(U21-SS1_PG1)") (class "Default")
      (node (ref "C150") (pin "2") (pinfunction "2_2") (pintype "passive"))
      (node (ref "U21") (pin "45") (pinfunction "SS1_PG1_45") (pintype "bidirectional"))
    )
    (net (code "32") (name "Net-(U21-SS2_PG2)") (class "Default")
      (node (ref "C156") (pin "2") (pinfunction "2_2") (pintype "passive"))
      (node (ref "U21") (pin "16") (pinfunction "SS2_PG2_16") (pintype "bidirectional"))
    )
    (net (code "33") (name "Net-(U21-SS3_PG3)") (class "Default")
      (node (ref "C162") (pin "2") (pinfunction "2_2") (pintype "passive"))
      (node (ref "U21") (pin "24") (pinfunction "SS3_PG3_24") (pintype "bidirectional"))
    )
    (net (code "34") (name "Net-(U21-SS4_PG4)") (class "Default")
      (node (ref "C168") (pin "2") (pinfunction "2_2") (pintype "passive"))
      (node (ref "U21") (pin "37") (pinfunction "SS4_PG4_37") (pintype "bidirectional"))
    )
    (net (code "35") (name "Net-(U21-SW3)") (class "Default")
      (node (ref "C157") (pin "1") (pinfunction "1_1") (pintype "passive"))
      (node (ref "L11") (pin "2") (pintype "passive"))
      (node (ref "U21") (pin "29") (pinfunction "SW3_29") (pintype "power_in"))
    )
    (net (code "36") (name "Net-(U21-SW4)") (class "Default")
      (node (ref "C163") (pin "1") (pinfunction "1_1") (pintype "passive"))
      (node (ref "L12") (pin "2") (pintype "passive"))
      (node (ref "U21") (pin "32") (pinfunction "SW4_32") (pintype "power_in"))
    )
    (net (code "37") (name "Net-(U21-VDDA)") (class "Default")
      (node (ref "C173") (pin "2") (pinfunction "2_2") (pintype "passive"))
      (node (ref "U21") (pin "19") (pinfunction "VDDA_19") (pintype "power_in"))
    )
    (net (code "38") (name "Net-(U21-VDDG)") (class "Default")
      (node (ref "C172") (pin "2") (pinfunction "2_2") (pintype "passive"))
      (node (ref "U21") (pin "18") (pinfunction "VDDG_18") (pintype "power_in"))
    )
    (net (code "39") (name "Net-(U21-VFB1)") (class "Default")
      (node (ref "R187") (pin "2") (pinfunction "2_2") (pintype "passive"))
      (node (ref "R188") (pin "1") (pinfunction "1_1") (pintype "passive"))
      (node (ref "U21") (pin "47") (pinfunction "VFB1_47") (pintype "input"))
    )
    (net (code "40") (name "Net-(U21-VFB2)") (class "Default")
      (node (ref "R191") (pin "2") (pinfunction "2_2") (pintype "passive"))
      (node (ref "R192") (pin "1") (pinfunction "1_1") (pintype "passive"))
      (node (ref "U21") (pin "14") (pinfunction "VFB2_14") (pintype "input"))
    )
    (net (code "41") (name "Net-(U21-VFB3)") (class "Default")
      (node (ref "R195") (pin "2") (pinfunction "2_2") (pintype "passive"))
      (node (ref "R196") (pin "1") (pinfunction "1_1") (pintype "passive"))
      (node (ref "U21") (pin "26") (pinfunction "VFB3_26") (pintype "input"))
    )
    (net (code "42") (name "Net-(U21-VFB4)") (class "Default")
      (node (ref "R199") (pin "2") (pinfunction "2_2") (pintype "passive"))
      (node (ref "R200") (pin "1") (pinfunction "1_1") (pintype "passive"))
      (node (ref "U21") (pin "35") (pinfunction "VFB4_35") (pintype "input"))
    )
    (net (code "43") (name "V2P5") (class "Default")
      (node (ref "C165") (pin "2") (pinfunction "2_2") (pintype "passive"))
      (node (ref "L12") (pin "1") (pintype "passive"))
      (node (ref "R199") (pin "1") (pinfunction "1_1") (pintype "passive"))
    )
    (net (code "44") (name "V3P3") (class "Default")
      (node (ref "C153") (pin "2") (pinfunction "2_2") (pintype "passive"))
      (node (ref "L10") (pin "1") (pintype "passive"))
      (node (ref "R191") (pin "1") (pinfunction "1_1") (pintype "passive"))
    )
    (net (code "45") (name "V5P0") (class "Default")
      (node (ref "C147") (pin "2") (pinfunction "2_2") (pintype "passive"))
      (node (ref "L9") (pin "1") (pintype "passive"))
      (node (ref "R187") (pin "1") (pinfunction "1_1") (pintype "passive"))
    )
    (net (code "46") (name "VADJ") (class "Default")
      (node (ref "C159") (pin "2") (pinfunction "2_2") (pintype "passive"))
      (node (ref "L11") (pin "1") (pintype "passive"))
      (node (ref "R195") (pin "1") (pinfunction "1_1") (pintype "passive"))
    )
    (net (code "47") (name "VDDD_V3P3") (class "Default")
      (node (ref "C171") (pin "2") (pinfunction "2_2") (pintype "passive"))
      (node (ref "R185") (pin "1") (pinfunction "1_1") (pintype "passive"))
      (node (ref "R189") (pin "1") (pinfunction "1_1") (pintype "passive"))
      (node (ref "R193") (pin "1") (pinfunction "1_1") (pintype "passive"))
      (node (ref "R197") (pin "1") (pinfunction "1_1") (pintype "passive"))
      (node (ref "R201") (pin "2") (pinfunction "2_2") (pintype "passive"))
      (node (ref "R203") (pin "1") (pinfunction "1_1") (pintype "passive"))
      (node (ref "U21") (pin "20") (pinfunction "VDDD_20") (pintype "power_in"))
    )
    (net (code "48") (name "VSYS") (class "Default")
      (node (ref "C146") (pin "2") (pinfunction "2_2") (pintype "passive"))
      (node (ref "C152") (pin "2") (pinfunction "2_2") (pintype "passive"))
      (node (ref "C158") (pin "2") (pinfunction "2_2") (pintype "passive"))
      (node (ref "C164") (pin "2") (pinfunction "2_2") (pintype "passive"))
      (node (ref "C169") (pin "2") (pinfunction "2_2") (pintype "passive"))
      (node (ref "C170") (pin "2") (pinfunction "2_2") (pintype "passive"))
      (node (ref "U21") (pin "22") (pinfunction "VIN_22") (pintype "power_in"))
      (node (ref "U21") (pin "30") (pinfunction "PVIN3_30") (pintype "power_in"))
      (node (ref "U21") (pin "31") (pinfunction "PVIN4_31") (pintype "power_in"))
      (node (ref "U21") (pin "5") (pinfunction "PVIN1_5") (pintype "power_in"))
      (node (ref "U21") (pin "6") (pinfunction "PVIN2_6") (pintype "power_in"))
    )
    (net (code "49") (name "unconnected-(U21-CLK_OUT-Pad44)") (class "Default")
      (node (ref "U21") (pin "44") (pinfunction "CLK_OUT_44") (pintype "output+no_connect"))
    )
  )
)
